# mpc57_cpuio2.net
KiCad netlist of a schematic drawn in Altium Designer
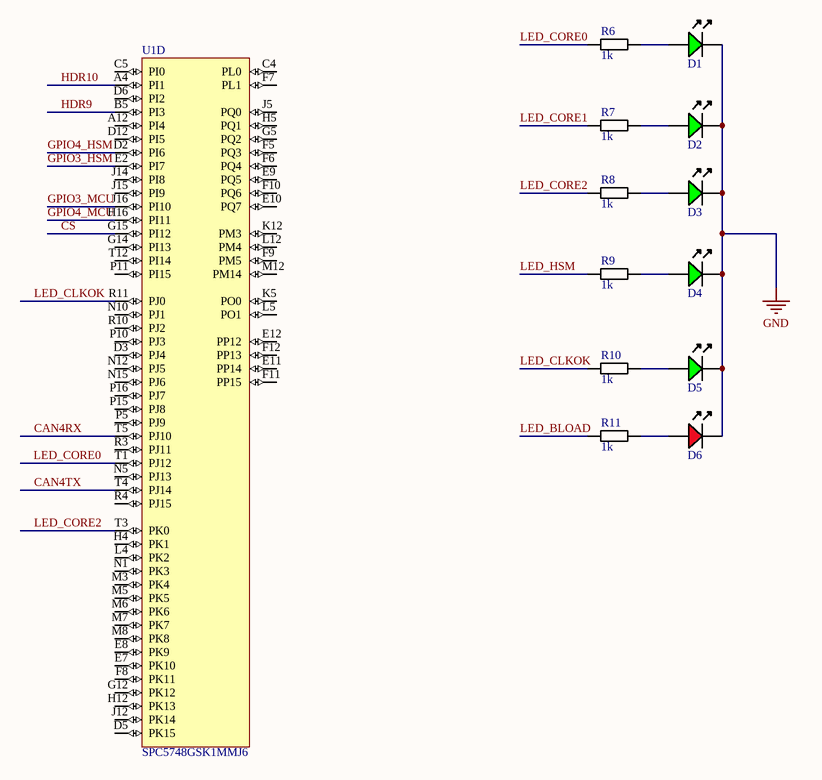
[diagram p0: mpc57_cpuio2.SchDoc]

(export (version "E")
  (design (tool "Eeschema 10.0.6"))
  (components
    (comp (ref "D1")
      (value "LED, 0603, Green")
      (footprint "LED-0603-GREEN")
      (description "Chip LED, Green")
      (fields (field (name "PART NUMBER") "LEDCHIP_0603_GREEN"))
      (libsource (lib "NewAE_AltiumLib") (part "LED_GREEN"))
    )
    (comp (ref "D2")
      (value "LED, 0603, Green")
      (footprint "LED-0603-GREEN")
      (description "Chip LED, Green")
      (fields (field (name "PART NUMBER") "LEDCHIP_0603_GREEN"))
      (libsource (lib "NewAE_AltiumLib") (part "LED_GREEN"))
    )
    (comp (ref "D3")
      (value "LED, 0603, Green")
      (footprint "LED-0603-GREEN")
      (description "Chip LED, Green")
      (fields (field (name "PART NUMBER") "LEDCHIP_0603_GREEN"))
      (libsource (lib "NewAE_AltiumLib") (part "LED_GREEN"))
    )
    (comp (ref "D4")
      (value "LED, 0603, Green")
      (footprint "LED-0603-GREEN")
      (description "Chip LED, Green")
      (fields (field (name "PART NUMBER") "LEDCHIP_0603_GREEN"))
      (libsource (lib "NewAE_AltiumLib") (part "LED_GREEN"))
    )
    (comp (ref "D5")
      (value "LED, 0603, Green")
      (footprint "LED-0603-GREEN")
      (description "Chip LED, Green")
      (fields (field (name "PART NUMBER") "LEDCHIP_0603_GREEN"))
      (libsource (lib "NewAE_AltiumLib") (part "LED_GREEN"))
    )
    (comp (ref "D6")
      (value "LED, 0603, Red")
      (footprint "LED-0603-RED")
      (description "Chip LED, Red")
      (fields (field (name "PART NUMBER") "LEDCHIP_0603_RED"))
      (libsource (lib "NewAE_AltiumLib") (part "LED_RED"))
    )
    (comp (ref "R6")
      (value "1k")
      (footprint "RESC1608X55N")
      (description "1k res, 0603, 1%, 1/10W")
      (fields (field (name "PART NUMBER") "RCHIP-1K-0603") (field (name "TOLERANCE") "1%"))
      (libsource (lib "NewAE_AltiumLib") (part "RES-EU"))
    )
    (comp (ref "R7")
      (value "1k")
      (footprint "RESC1608X55N")
      (description "1k res, 0603, 1%, 1/10W")
      (fields (field (name "PART NUMBER") "RCHIP-1K-0603") (field (name "TOLERANCE") "1%"))
      (libsource (lib "NewAE_AltiumLib") (part "RES-EU"))
    )
    (comp (ref "R8")
      (value "1k")
      (footprint "RESC1608X55N")
      (description "1k res, 0603, 1%, 1/10W")
      (fields (field (name "PART NUMBER") "RCHIP-1K-0603") (field (name "TOLERANCE") "1%"))
      (libsource (lib "NewAE_AltiumLib") (part "RES-EU"))
    )
    (comp (ref "R9")
      (value "1k")
      (footprint "RESC1608X55N")
      (description "1k res, 0603, 1%, 1/10W")
      (fields (field (name "PART NUMBER") "RCHIP-1K-0603") (field (name "TOLERANCE") "1%"))
      (libsource (lib "NewAE_AltiumLib") (part "RES-EU"))
    )
    (comp (ref "R10")
      (value "1k")
      (footprint "RESC1608X55N")
      (description "1k res, 0603, 1%, 1/10W")
      (fields (field (name "PART NUMBER") "RCHIP-1K-0603") (field (name "TOLERANCE") "1%"))
      (libsource (lib "NewAE_AltiumLib") (part "RES-EU"))
    )
    (comp (ref "R11")
      (value "1k")
      (footprint "RESC1608X55N")
      (description "1k res, 0603, 1%, 1/10W")
      (fields (field (name "PART NUMBER") "RCHIP-1K-0603") (field (name "TOLERANCE") "1%"))
      (libsource (lib "NewAE_AltiumLib") (part "RES-EU"))
    )
    (comp (ref "U1")
      (value "SPC5748GSK1MMJ6")
      (footprint "NewAE_AltiumLib:BGA256C100P16X16_1700X1700X170")
      (description "Freescale 32-bit MCU, Triple core, 6MB Flash, 160MHz, -40/+125degC, Automotive Qualified, BGA 256")
      (libsource (lib "NewAE_AltiumLib") (part "SPC5748GSK1MMJ6"))
    )
  )
  (nets
    (net (code "1") (name "/CAN4RX") (class "Default")
      (node (ref "U1") (pin "T5") (pinfunction "PJ10_T5") (pintype "bidirectional"))
    )
    (net (code "2") (name "/CAN4TX") (class "Default")
      (node (ref "U1") (pin "T4") (pinfunction "PJ14_T4") (pintype "bidirectional"))
    )
    (net (code "3") (name "/CS") (class "Default")
      (node (ref "U1") (pin "G15") (pinfunction "PI12_G15") (pintype "bidirectional"))
    )
    (net (code "4") (name "/GPIO3_HSM") (class "Default")
      (node (ref "U1") (pin "E2") (pinfunction "PI7_E2") (pintype "bidirectional"))
    )
    (net (code "5") (name "/GPIO3_MCU") (class "Default")
      (node (ref "U1") (pin "J16") (pinfunction "PI10_J16") (pintype "bidirectional"))
    )
    (net (code "6") (name "/GPIO4_HSM") (class "Default")
      (node (ref "U1") (pin "D2") (pinfunction "PI6_D2") (pintype "bidirectional"))
    )
    (net (code "7") (name "/GPIO4_MCU") (class "Default")
      (node (ref "U1") (pin "H16") (pinfunction "PI11_H16") (pintype "bidirectional"))
    )
    (net (code "8") (name "/HDR9") (class "Default")
      (node (ref "U1") (pin "B5") (pinfunction "PI3_B5") (pintype "bidirectional"))
    )
    (net (code "9") (name "/HDR10") (class "Default")
      (node (ref "U1") (pin "A4") (pinfunction "PI1_A4") (pintype "bidirectional"))
    )
    (net (code "10") (name "/LED_BLOAD") (class "Default")
      (node (ref "R11") (pin "1") (pinfunction "1_1") (pintype "passive"))
    )
    (net (code "11") (name "/LED_CLKOK") (class "Default")
      (node (ref "R10") (pin "1") (pinfunction "1_1") (pintype "passive"))
      (node (ref "U1") (pin "R11") (pinfunction "PJ0_R11") (pintype "bidirectional"))
    )
    (net (code "12") (name "/LED_CORE0") (class "Default")
      (node (ref "R6") (pin "1") (pinfunction "1_1") (pintype "passive"))
      (node (ref "U1") (pin "T1") (pinfunction "PJ12_T1") (pintype "bidirectional"))
    )
    (net (code "13") (name "/LED_CORE1") (class "Default")
      (node (ref "R7") (pin "1") (pinfunction "1_1") (pintype "passive"))
    )
    (net (code "14") (name "/LED_CORE2") (class "Default")
      (node (ref "R8") (pin "1") (pinfunction "1_1") (pintype "passive"))
      (node (ref "U1") (pin "T3") (pinfunction "PK0_T3") (pintype "bidirectional"))
    )
    (net (code "15") (name "/LED_HSM") (class "Default")
      (node (ref "R9") (pin "1") (pinfunction "1_1") (pintype "passive"))
    )
    (net (code "16") (name "GND") (class "Default")
      (node (ref "D1") (pin "K") (pinfunction "K_K") (pintype "passive"))
      (node (ref "D2") (pin "K") (pinfunction "K_K") (pintype "passive"))
      (node (ref "D3") (pin "K") (pinfunction "K_K") (pintype "passive"))
      (node (ref "D4") (pin "K") (pinfunction "K_K") (pintype "passive"))
      (node (ref "D5") (pin "K") (pinfunction "K_K") (pintype "passive"))
      (node (ref "D6") (pin "K") (pinfunction "K_K") (pintype "passive"))
    )
    (net (code "17") (name "Net-(D1-PadA)") (class "Default")
      (node (ref "D1") (pin "A") (pinfunction "A_A") (pintype "passive"))
      (node (ref "R6") (pin "2") (pinfunction "2_2") (pintype "passive"))
    )
    (net (code "18") (name "Net-(D2-PadA)") (class "Default")
      (node (ref "D2") (pin "A") (pinfunction "A_A") (pintype "passive"))
      (node (ref "R7") (pin "2") (pinfunction "2_2") (pintype "passive"))
    )
    (net (code "19") (name "Net-(D3-PadA)") (class "Default")
      (node (ref "D3") (pin "A") (pinfunction "A_A") (pintype "passive"))
      (node (ref "R8") (pin "2") (pinfunction "2_2") (pintype "passive"))
    )
    (net (code "20") (name "Net-(D4-PadA)") (class "Default")
      (node (ref "D4") (pin "A") (pinfunction "A_A") (pintype "passive"))
      (node (ref "R9") (pin "2") (pinfunction "2_2") (pintype "passive"))
    )
    (net (code "21") (name "Net-(D5-PadA)") (class "Default")
      (node (ref "D5") (pin "A") (pinfunction "A_A") (pintype "passive"))
      (node (ref "R10") (pin "2") (pinfunction "2_2") (pintype "passive"))
    )
    (net (code "22") (name "Net-(D6-PadA)") (class "Default")
      (node (ref "D6") (pin "A") (pinfunction "A_A") (pintype "passive"))
      (node (ref "R11") (pin "2") (pinfunction "2_2") (pintype "passive"))
    )
    (net (code "23") (name "unconnected-(U1D-PI0-PadC5)") (class "Default")
      (node (ref "U1") (pin "C5") (pinfunction "PI0_C5") (pintype "bidirectional"))
    )
    (net (code "24") (name "unconnected-(U1D-PI2-PadD6)") (class "Default")
      (node (ref "U1") (pin "D6") (pinfunction "PI2_D6") (pintype "bidirectional"))
    )
    (net (code "25") (name "unconnected-(U1D-PI4-PadA12)") (class "Default")
      (node (ref "U1") (pin "A12") (pinfunction "PI4_A12") (pintype "bidirectional"))
    )
    (net (code "26") (name "unconnected-(U1D-PI5-PadD12)") (class "Default")
      (node (ref "U1") (pin "D12") (pinfunction "PI5_D12") (pintype "bidirectional"))
    )
    (net (code "27") (name "unconnected-(U1D-PI8-PadJ14)") (class "Default")
      (node (ref "U1") (pin "J14") (pinfunction "PI8_J14") (pintype "bidirectional"))
    )
    (net (code "28") (name "unconnected-(U1D-PI9-PadJ15)") (class "Default")
      (node (ref "U1") (pin "J15") (pinfunction "PI9_J15") (pintype "bidirectional"))
    )
    (net (code "29") (name "unconnected-(U1D-PI13-PadG14)") (class "Default")
      (node (ref "U1") (pin "G14") (pinfunction "PI13_G14") (pintype "bidirectional"))
    )
    (net (code "30") (name "unconnected-(U1D-PI14-PadT12)") (class "Default")
      (node (ref "U1") (pin "T12") (pinfunction "PI14_T12") (pintype "bidirectional"))
    )
    (net (code "31") (name "unconnected-(U1D-PI15-PadP11)") (class "Default")
      (node (ref "U1") (pin "P11") (pinfunction "PI15_P11") (pintype "bidirectional"))
    )
    (net (code "32") (name "unconnected-(U1D-PJ1-PadN10)") (class "Default")
      (node (ref "U1") (pin "N10") (pinfunction "PJ1_N10") (pintype "bidirectional"))
    )
    (net (code "33") (name "unconnected-(U1D-PJ2-PadR10)") (class "Default")
      (node (ref "U1") (pin "R10") (pinfunction "PJ2_R10") (pintype "bidirectional"))
    )
    (net (code "34") (name "unconnected-(U1D-PJ3-PadP10)") (class "Default")
      (node (ref "U1") (pin "P10") (pinfunction "PJ3_P10") (pintype "bidirectional"))
    )
    (net (code "35") (name "unconnected-(U1D-PJ4-PadD3)") (class "Default")
      (node (ref "U1") (pin "D3") (pinfunction "PJ4_D3") (pintype "bidirectional"))
    )
    (net (code "36") (name "unconnected-(U1D-PJ5-PadN12)") (class "Default")
      (node (ref "U1") (pin "N12") (pinfunction "PJ5_N12") (pintype "bidirectional"))
    )
    (net (code "37") (name "unconnected-(U1D-PJ6-PadN15)") (class "Default")
      (node (ref "U1") (pin "N15") (pinfunction "PJ6_N15") (pintype "bidirectional"))
    )
    (net (code "38") (name "unconnected-(U1D-PJ7-PadP16)") (class "Default")
      (node (ref "U1") (pin "P16") (pinfunction "PJ7_P16") (pintype "bidirectional"))
    )
    (net (code "39") (name "unconnected-(U1D-PJ8-PadP15)") (class "Default")
      (node (ref "U1") (pin "P15") (pinfunction "PJ8_P15") (pintype "bidirectional"))
    )
    (net (code "40") (name "unconnected-(U1D-PJ9-PadP5)") (class "Default")
      (node (ref "U1") (pin "P5") (pinfunction "PJ9_P5") (pintype "bidirectional"))
    )
    (net (code "41") (name "unconnected-(U1D-PJ11-PadR3)") (class "Default")
      (node (ref "U1") (pin "R3") (pinfunction "PJ11_R3") (pintype "bidirectional"))
    )
    (net (code "42") (name "unconnected-(U1D-PJ13-PadN5)") (class "Default")
      (node (ref "U1") (pin "N5") (pinfunction "PJ13_N5") (pintype "bidirectional"))
    )
    (net (code "43") (name "unconnected-(U1D-PJ15-PadR4)") (class "Default")
      (node (ref "U1") (pin "R4") (pinfunction "PJ15_R4") (pintype "bidirectional"))
    )
    (net (code "44") (name "unconnected-(U1D-PK1-PadH4)") (class "Default")
      (node (ref "U1") (pin "H4") (pinfunction "PK1_H4") (pintype "bidirectional"))
    )
    (net (code "45") (name "unconnected-(U1D-PK2-PadL4)") (class "Default")
      (node (ref "U1") (pin "L4") (pinfunction "PK2_L4") (pintype "bidirectional"))
    )
    (net (code "46") (name "unconnected-(U1D-PK3-PadN1)") (class "Default")
      (node (ref "U1") (pin "N1") (pinfunction "PK3_N1") (pintype "bidirectional"))
    )
    (net (code "47") (name "unconnected-(U1D-PK4-PadM3)") (class "Default")
      (node (ref "U1") (pin "M3") (pinfunction "PK4_M3") (pintype "bidirectional"))
    )
    (net (code "48") (name "unconnected-(U1D-PK5-PadM5)") (class "Default")
      (node (ref "U1") (pin "M5") (pinfunction "PK5_M5") (pintype "bidirectional"))
    )
    (net (code "49") (name "unconnected-(U1D-PK6-PadM6)") (class "Default")
      (node (ref "U1") (pin "M6") (pinfunction "PK6_M6") (pintype "bidirectional"))
    )
    (net (code "50") (name "unconnected-(U1D-PK7-PadM7)") (class "Default")
      (node (ref "U1") (pin "M7") (pinfunction "PK7_M7") (pintype "bidirectional"))
    )
    (net (code "51") (name "unconnected-(U1D-PK8-PadM8)") (class "Default")
      (node (ref "U1") (pin "M8") (pinfunction "PK8_M8") (pintype "bidirectional"))
    )
    (net (code "52") (name "unconnected-(U1D-PK9-PadE8)") (class "Default")
      (node (ref "U1") (pin "E8") (pinfunction "PK9_E8") (pintype "bidirectional"))
    )
    (net (code "53") (name "unconnected-(U1D-PK10-PadE7)") (class "Default")
      (node (ref "U1") (pin "E7") (pinfunction "PK10_E7") (pintype "bidirectional"))
    )
    (net (code "54") (name "unconnected-(U1D-PK11-PadF8)") (class "Default")
      (node (ref "U1") (pin "F8") (pinfunction "PK11_F8") (pintype "bidirectional"))
    )
    (net (code "55") (name "unconnected-(U1D-PK12-PadG12)") (class "Default")
      (node (ref "U1") (pin "G12") (pinfunction "PK12_G12") (pintype "bidirectional"))
    )
    (net (code "56") (name "unconnected-(U1D-PK13-PadH12)") (class "Default")
      (node (ref "U1") (pin "H12") (pinfunction "PK13_H12") (pintype "bidirectional"))
    )
    (net (code "57") (name "unconnected-(U1D-PK14-PadJ12)") (class "Default")
      (node (ref "U1") (pin "J12") (pinfunction "PK14_J12") (pintype "bidirectional"))
    )
    (net (code "58") (name "unconnected-(U1D-PK15-PadD5)") (class "Default")
      (node (ref "U1") (pin "D5") (pinfunction "PK15_D5") (pintype "bidirectional"))
    )
    (net (code "59") (name "unconnected-(U1D-PL0-PadC4)") (class "Default")
      (node (ref "U1") (pin "C4") (pinfunction "PL0_C4") (pintype "bidirectional"))
    )
    (net (code "60") (name "unconnected-(U1D-PL1-PadF7)") (class "Default")
      (node (ref "U1") (pin "F7") (pinfunction "PL1_F7") (pintype "bidirectional"))
    )
    (net (code "61") (name "unconnected-(U1D-PM3-PadK12)") (class "Default")
      (node (ref "U1") (pin "K12") (pinfunction "PM3_K12") (pintype "bidirectional"))
    )
    (net (code "62") (name "unconnected-(U1D-PM4-PadL12)") (class "Default")
      (node (ref "U1") (pin "L12") (pinfunction "PM4_L12") (pintype "bidirectional"))
    )
    (net (code "63") (name "unconnected-(U1D-PM5-PadF9)") (class "Default")
      (node (ref "U1") (pin "F9") (pinfunction "PM5_F9") (pintype "bidirectional"))
    )
    (net (code "64") (name "unconnected-(U1D-PM14-PadM12)") (class "Default")
      (node (ref "U1") (pin "M12") (pinfunction "PM14_M12") (pintype "bidirectional"))
    )
    (net (code "65") (name "unconnected-(U1D-PO0-PadK5)") (class "Default")
      (node (ref "U1") (pin "K5") (pinfunction "PO0_K5") (pintype "bidirectional"))
    )
    (net (code "66") (name "unconnected-(U1D-PO1-PadL5)") (class "Default")
      (node (ref "U1") (pin "L5") (pinfunction "PO1_L5") (pintype "bidirectional"))
    )
    (net (code "67") (name "unconnected-(U1D-PP12-PadE12)") (class "Default")
      (node (ref "U1") (pin "E12") (pinfunction "PP12_E12") (pintype "bidirectional"))
    )
    (net (code "68") (name "unconnected-(U1D-PP13-PadF12)") (class "Default")
      (node (ref "U1") (pin "F12") (pinfunction "PP13_F12") (pintype "bidirectional"))
    )
    (net (code "69") (name "unconnected-(U1D-PP14-PadE11)") (class "Default")
      (node (ref "U1") (pin "E11") (pinfunction "PP14_E11") (pintype "bidirectional"))
    )
    (net (code "70") (name "unconnected-(U1D-PP15-PadF11)") (class "Default")
      (node (ref "U1") (pin "F11") (pinfunction "PP15_F11") (pintype "bidirectional"))
    )
    (net (code "71") (name "unconnected-(U1D-PQ0-PadJ5)") (class "Default")
      (node (ref "U1") (pin "J5") (pinfunction "PQ0_J5") (pintype "bidirectional"))
    )
    (net (code "72") (name "unconnected-(U1D-PQ1-PadH5)") (class "Default")
      (node (ref "U1") (pin "H5") (pinfunction "PQ1_H5") (pintype "bidirectional"))
    )
    (net (code "73") (name "unconnected-(U1D-PQ2-PadG5)") (class "Default")
      (node (ref "U1") (pin "G5") (pinfunction "PQ2_G5") (pintype "bidirectional"))
    )
    (net (code "74") (name "unconnected-(U1D-PQ3-PadF5)") (class "Default")
      (node (ref "U1") (pin "F5") (pinfunction "PQ3_F5") (pintype "bidirectional"))
    )
    (net (code "75") (name "unconnected-(U1D-PQ4-PadF6)") (class "Default")
      (node (ref "U1") (pin "F6") (pinfunction "PQ4_F6") (pintype "bidirectional"))
    )
    (net (code "76") (name "unconnected-(U1D-PQ5-PadE9)") (class "Default")
      (node (ref "U1") (pin "E9") (pinfunction "PQ5_E9") (pintype "bidirectional"))
    )
    (net (code "77") (name "unconnected-(U1D-PQ6-PadF10)") (class "Default")
      (node (ref "U1") (pin "F10") (pinfunction "PQ6_F10") (pintype "bidirectional"))
    )
    (net (code "78") (name "unconnected-(U1D-PQ7-PadE10)") (class "Default")
      (node (ref "U1") (pin "E10") (pinfunction "PQ7_E10") (pintype "bidirectional"))
    )
  )
)
